# MotorShield.net
KiCad netlist of a schematic drawn in EAGLE
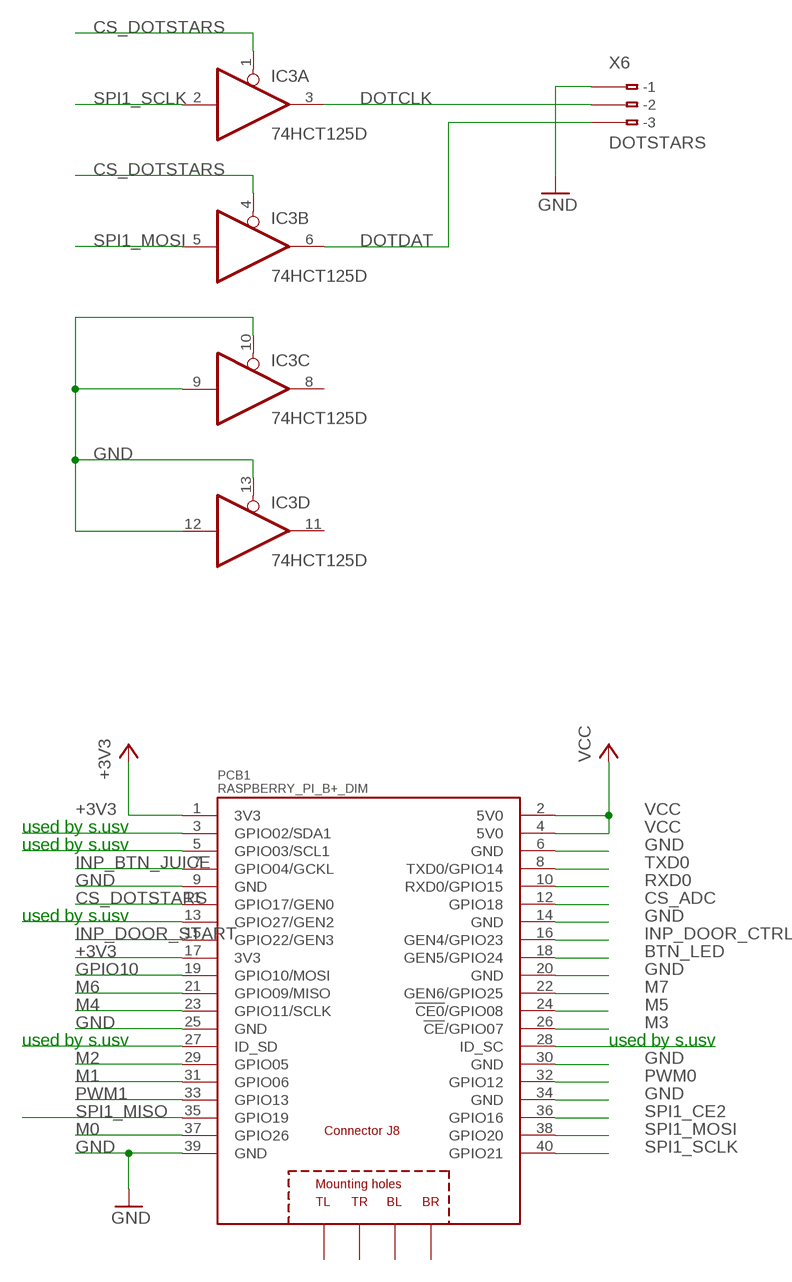
[diagram p0: schematic, sheet 1, part 1 of 2]
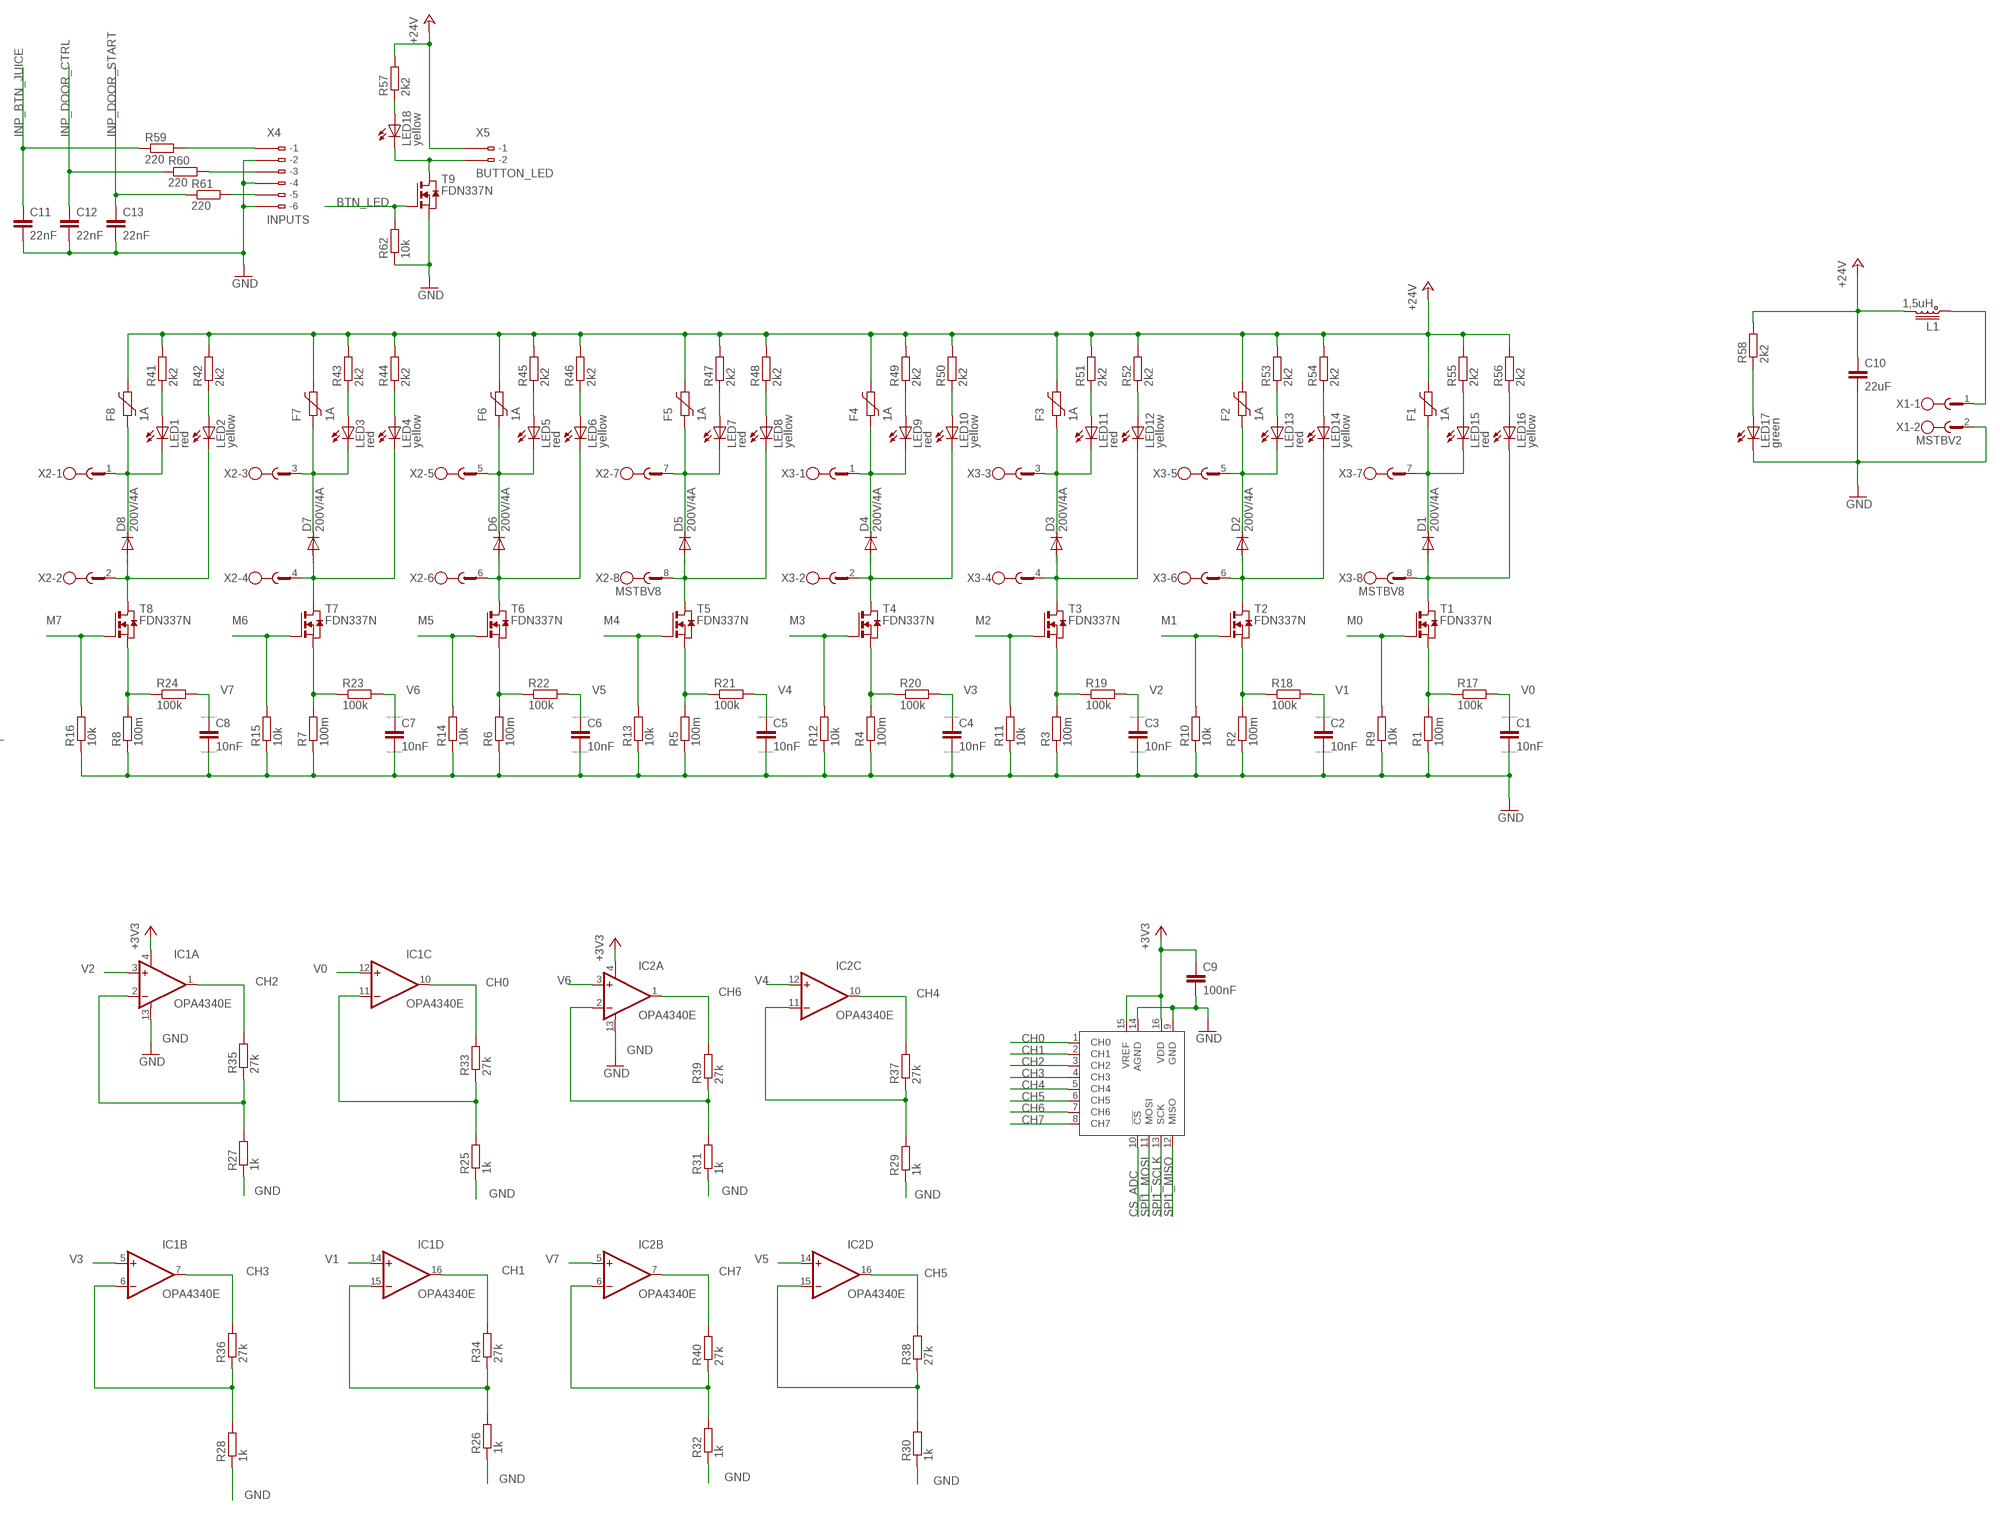
[diagram p1: schematic, sheet 1, part 2 of 2]

(export (version "E")
  (design (tool "Eeschema 10.0.6"))
  (components
    (comp (ref "C1")
      (value "10nF")
      (footprint "eagle-import:C0805")
      (libsource (lib "eagle-import") (part "C"))
    )
    (comp (ref "C2")
      (value "10nF")
      (footprint "eagle-import:C0805")
      (libsource (lib "eagle-import") (part "C"))
    )
    (comp (ref "C3")
      (value "10nF")
      (footprint "eagle-import:C0805")
      (libsource (lib "eagle-import") (part "C"))
    )
    (comp (ref "C4")
      (value "10nF")
      (footprint "eagle-import:C0805")
      (libsource (lib "eagle-import") (part "C"))
    )
    (comp (ref "C5")
      (value "10nF")
      (footprint "eagle-import:C0805")
      (libsource (lib "eagle-import") (part "C"))
    )
    (comp (ref "C6")
      (value "10nF")
      (footprint "eagle-import:C0805")
      (libsource (lib "eagle-import") (part "C"))
    )
    (comp (ref "C7")
      (value "10nF")
      (footprint "eagle-import:C0805")
      (libsource (lib "eagle-import") (part "C"))
    )
    (comp (ref "C8")
      (value "10nF")
      (footprint "eagle-import:C0805")
      (libsource (lib "eagle-import") (part "C"))
    )
    (comp (ref "C9")
      (value "100nF")
      (footprint "eagle-import:C0805")
      (libsource (lib "eagle-import") (part "C-EUC0805"))
    )
    (comp (ref "C10")
      (value "22uF")
      (footprint "eagle-import:C1812")
      (libsource (lib "eagle-import") (part "C-EUC1812"))
    )
    (comp (ref "C11")
      (value "22nF")
      (footprint "eagle-import:C0805K")
      (libsource (lib "eagle-import") (part "C-EUC0805K"))
    )
    (comp (ref "C12")
      (value "22nF")
      (footprint "eagle-import:C0805K")
      (libsource (lib "eagle-import") (part "C-EUC0805K"))
    )
    (comp (ref "C13")
      (value "22nF")
      (footprint "eagle-import:C0805K")
      (libsource (lib "eagle-import") (part "C-EUC0805K"))
    )
    (comp (ref "D1")
      (value "200V/4A")
      (footprint "eagle-import:DO214AA")
      (libsource (lib "eagle-import") (part "DIODE-DO214AA"))
    )
    (comp (ref "D2")
      (value "200V/4A")
      (footprint "eagle-import:DO214AA")
      (libsource (lib "eagle-import") (part "DIODE-DO214AA"))
    )
    (comp (ref "D3")
      (value "200V/4A")
      (footprint "eagle-import:DO214AA")
      (libsource (lib "eagle-import") (part "DIODE-DO214AA"))
    )
    (comp (ref "D4")
      (value "200V/4A")
      (footprint "eagle-import:DO214AA")
      (libsource (lib "eagle-import") (part "DIODE-DO214AA"))
    )
    (comp (ref "D5")
      (value "200V/4A")
      (footprint "eagle-import:DO214AA")
      (libsource (lib "eagle-import") (part "DIODE-DO214AA"))
    )
    (comp (ref "D6")
      (value "200V/4A")
      (footprint "eagle-import:DO214AA")
      (libsource (lib "eagle-import") (part "DIODE-DO214AA"))
    )
    (comp (ref "D7")
      (value "200V/4A")
      (footprint "eagle-import:DO214AA")
      (libsource (lib "eagle-import") (part "DIODE-DO214AA"))
    )
    (comp (ref "D8")
      (value "200V/4A")
      (footprint "eagle-import:DO214AA")
      (libsource (lib "eagle-import") (part "DIODE-DO214AA"))
    )
    (comp (ref "F1")
      (value "1A")
      (footprint "eagle-import:1812L")
      (libsource (lib "eagle-import") (part "1812L"))
    )
    (comp (ref "F2")
      (value "1A")
      (footprint "eagle-import:1812L")
      (libsource (lib "eagle-import") (part "1812L"))
    )
    (comp (ref "F3")
      (value "1A")
      (footprint "eagle-import:1812L")
      (libsource (lib "eagle-import") (part "1812L"))
    )
    (comp (ref "F4")
      (value "1A")
      (footprint "eagle-import:1812L")
      (libsource (lib "eagle-import") (part "1812L"))
    )
    (comp (ref "F5")
      (value "1A")
      (footprint "eagle-import:1812L")
      (libsource (lib "eagle-import") (part "1812L"))
    )
    (comp (ref "F6")
      (value "1A")
      (footprint "eagle-import:1812L")
      (libsource (lib "eagle-import") (part "1812L"))
    )
    (comp (ref "F7")
      (value "1A")
      (footprint "eagle-import:1812L")
      (libsource (lib "eagle-import") (part "1812L"))
    )
    (comp (ref "F8")
      (value "1A")
      (footprint "eagle-import:1812L")
      (libsource (lib "eagle-import") (part "1812L"))
    )
    (comp (ref "IC1")
      (value "OPA4340E")
      (footprint "eagle-import:SSOP16BU")
      (fields (field (name "MPN") "OPA4340EA/250G4"))
      (libsource (lib "eagle-import") (part "OPA4340E"))
    )
    (comp (ref "IC2")
      (value "OPA4340E")
      (footprint "eagle-import:SSOP16BU")
      (fields (field (name "MPN") "OPA4340EA/250G4"))
      (libsource (lib "eagle-import") (part "OPA4340E"))
    )
    (comp (ref "IC3")
      (value "74HCT125D")
      (footprint "eagle-import:SO14")
      (libsource (lib "eagle-import") (part "74125DHCT"))
    )
    (comp (ref "IC4")
      (value "MCP3008SL")
      (footprint "eagle-import:SO16")
      (libsource (lib "eagle-import") (part "MCP3008SL"))
    )
    (comp (ref "L1")
      (value "1,5uH")
      (footprint "eagle-import:MPI4040")
      (libsource (lib "eagle-import") (part "MPI4040R3-1R5-R"))
    )
    (comp (ref "LED1")
      (value "red")
      (footprint "eagle-import:CHIP-LED0805")
      (libsource (lib "eagle-import") (part "LEDCHIP-LED0805"))
    )
    (comp (ref "LED2")
      (value "yellow")
      (footprint "eagle-import:CHIP-LED0805")
      (libsource (lib "eagle-import") (part "LEDCHIP-LED0805"))
    )
    (comp (ref "LED3")
      (value "red")
      (footprint "eagle-import:CHIP-LED0805")
      (libsource (lib "eagle-import") (part "LEDCHIP-LED0805"))
    )
    (comp (ref "LED4")
      (value "yellow")
      (footprint "eagle-import:CHIP-LED0805")
      (libsource (lib "eagle-import") (part "LEDCHIP-LED0805"))
    )
    (comp (ref "LED5")
      (value "red")
      (footprint "eagle-import:CHIP-LED0805")
      (libsource (lib "eagle-import") (part "LEDCHIP-LED0805"))
    )
    (comp (ref "LED6")
      (value "yellow")
      (footprint "eagle-import:CHIP-LED0805")
      (libsource (lib "eagle-import") (part "LEDCHIP-LED0805"))
    )
    (comp (ref "LED7")
      (value "red")
      (footprint "eagle-import:CHIP-LED0805")
      (libsource (lib "eagle-import") (part "LEDCHIP-LED0805"))
    )
    (comp (ref "LED8")
      (value "yellow")
      (footprint "eagle-import:CHIP-LED0805")
      (libsource (lib "eagle-import") (part "LEDCHIP-LED0805"))
    )
    (comp (ref "LED9")
      (value "red")
      (footprint "eagle-import:CHIP-LED0805")
      (libsource (lib "eagle-import") (part "LEDCHIP-LED0805"))
    )
    (comp (ref "LED10")
      (value "yellow")
      (footprint "eagle-import:CHIP-LED0805")
      (libsource (lib "eagle-import") (part "LEDCHIP-LED0805"))
    )
    (comp (ref "LED11")
      (value "red")
      (footprint "eagle-import:CHIP-LED0805")
      (libsource (lib "eagle-import") (part "LEDCHIP-LED0805"))
    )
    (comp (ref "LED12")
      (value "yellow")
      (footprint "eagle-import:CHIP-LED0805")
      (libsource (lib "eagle-import") (part "LEDCHIP-LED0805"))
    )
    (comp (ref "LED13")
      (value "red")
      (footprint "eagle-import:CHIP-LED0805")
      (libsource (lib "eagle-import") (part "LEDCHIP-LED0805"))
    )
    (comp (ref "LED14")
      (value "yellow")
      (footprint "eagle-import:CHIP-LED0805")
      (libsource (lib "eagle-import") (part "LEDCHIP-LED0805"))
    )
    (comp (ref "LED15")
      (value "red")
      (footprint "eagle-import:CHIP-LED0805")
      (libsource (lib "eagle-import") (part "LEDCHIP-LED0805"))
    )
    (comp (ref "LED16")
      (value "yellow")
      (footprint "eagle-import:CHIP-LED0805")
      (libsource (lib "eagle-import") (part "LEDCHIP-LED0805"))
    )
    (comp (ref "LED17")
      (value "green")
      (footprint "eagle-import:CHIP-LED0805")
      (libsource (lib "eagle-import") (part "LEDCHIP-LED0805"))
    )
    (comp (ref "LED18")
      (value "yellow")
      (footprint "eagle-import:CHIP-LED0805")
      (libsource (lib "eagle-import") (part "LEDCHIP-LED0805"))
    )
    (comp (ref "PCB1")
      (value "RASPBERRY_PI_B+_DIM")
      (footprint "eagle-import:RASPBERRY_PI_BPLUS_DIM")
      (libsource (lib "eagle-import") (part "RASPBERRY_PI_B+_DIM"))
    )
    (comp (ref "R1")
      (value "100m")
      (footprint "eagle-import:R0805")
      (libsource (lib "eagle-import") (part "R-EU_R0805"))
    )
    (comp (ref "R2")
      (value "100m")
      (footprint "eagle-import:R0805")
      (libsource (lib "eagle-import") (part "R-EU_R0805"))
    )
    (comp (ref "R3")
      (value "100m")
      (footprint "eagle-import:R0805")
      (libsource (lib "eagle-import") (part "R-EU_R0805"))
    )
    (comp (ref "R4")
      (value "100m")
      (footprint "eagle-import:R0805")
      (libsource (lib "eagle-import") (part "R-EU_R0805"))
    )
    (comp (ref "R5")
      (value "100m")
      (footprint "eagle-import:R0805")
      (libsource (lib "eagle-import") (part "R-EU_R0805"))
    )
    (comp (ref "R6")
      (value "100m")
      (footprint "eagle-import:R0805")
      (libsource (lib "eagle-import") (part "R-EU_R0805"))
    )
    (comp (ref "R7")
      (value "100m")
      (footprint "eagle-import:R0805")
      (libsource (lib "eagle-import") (part "R-EU_R0805"))
    )
    (comp (ref "R8")
      (value "100m")
      (footprint "eagle-import:R0805")
      (libsource (lib "eagle-import") (part "R-EU_R0805"))
    )
    (comp (ref "R9")
      (value "10k")
      (footprint "eagle-import:R0805")
      (libsource (lib "eagle-import") (part "R-EU_R0805"))
    )
    (comp (ref "R10")
      (value "10k")
      (footprint "eagle-import:R0805")
      (libsource (lib "eagle-import") (part "R-EU_R0805"))
    )
    (comp (ref "R11")
      (value "10k")
      (footprint "eagle-import:R0805")
      (libsource (lib "eagle-import") (part "R-EU_R0805"))
    )
    (comp (ref "R12")
      (value "10k")
      (footprint "eagle-import:R0805")
      (libsource (lib "eagle-import") (part "R-EU_R0805"))
    )
    (comp (ref "R13")
      (value "10k")
      (footprint "eagle-import:R0805")
      (libsource (lib "eagle-import") (part "R-EU_R0805"))
    )
    (comp (ref "R14")
      (value "10k")
      (footprint "eagle-import:R0805")
      (libsource (lib "eagle-import") (part "R-EU_R0805"))
    )
    (comp (ref "R15")
      (value "10k")
      (footprint "eagle-import:R0805")
      (libsource (lib "eagle-import") (part "R-EU_R0805"))
    )
    (comp (ref "R16")
      (value "10k")
      (footprint "eagle-import:R0805")
      (libsource (lib "eagle-import") (part "R-EU_R0805"))
    )
    (comp (ref "R17")
      (value "100k")
      (footprint "eagle-import:R0805")
      (libsource (lib "eagle-import") (part "R-EU_R0805"))
    )
    (comp (ref "R18")
      (value "100k")
      (footprint "eagle-import:R0805")
      (libsource (lib "eagle-import") (part "R-EU_R0805"))
    )
    (comp (ref "R19")
      (value "100k")
      (footprint "eagle-import:R0805")
      (libsource (lib "eagle-import") (part "R-EU_R0805"))
    )
    (comp (ref "R20")
      (value "100k")
      (footprint "eagle-import:R0805")
      (libsource (lib "eagle-import") (part "R-EU_R0805"))
    )
    (comp (ref "R21")
      (value "100k")
      (footprint "eagle-import:R0805")
      (libsource (lib "eagle-import") (part "R-EU_R0805"))
    )
    (comp (ref "R22")
      (value "100k")
      (footprint "eagle-import:R0805")
      (libsource (lib "eagle-import") (part "R-EU_R0805"))
    )
    (comp (ref "R23")
      (value "100k")
      (footprint "eagle-import:R0805")
      (libsource (lib "eagle-import") (part "R-EU_R0805"))
    )
    (comp (ref "R24")
      (value "100k")
      (footprint "eagle-import:R0805")
      (libsource (lib "eagle-import") (part "R-EU_R0805"))
    )
    (comp (ref "R25")
      (value "1k")
      (footprint "eagle-import:R0805")
      (libsource (lib "eagle-import") (part "R-EU_R0805"))
    )
    (comp (ref "R26")
      (value "1k")
      (footprint "eagle-import:R0805")
      (libsource (lib "eagle-import") (part "R-EU_R0805"))
    )
    (comp (ref "R27")
      (value "1k")
      (footprint "eagle-import:R0805")
      (libsource (lib "eagle-import") (part "R-EU_R0805"))
    )
    (comp (ref "R28")
      (value "1k")
      (footprint "eagle-import:R0805")
      (libsource (lib "eagle-import") (part "R-EU_R0805"))
    )
    (comp (ref "R29")
      (value "1k")
      (footprint "eagle-import:R0805")
      (libsource (lib "eagle-import") (part "R-EU_R0805"))
    )
    (comp (ref "R30")
      (value "1k")
      (footprint "eagle-import:R0805")
      (libsource (lib "eagle-import") (part "R-EU_R0805"))
    )
    (comp (ref "R31")
      (value "1k")
      (footprint "eagle-import:R0805")
      (libsource (lib "eagle-import") (part "R-EU_R0805"))
    )
    (comp (ref "R32")
      (value "1k")
      (footprint "eagle-import:R0805")
      (libsource (lib "eagle-import") (part "R-EU_R0805"))
    )
    (comp (ref "R33")
      (value "27k")
      (footprint "eagle-import:R0805")
      (libsource (lib "eagle-import") (part "R-EU_R0805"))
    )
    (comp (ref "R34")
      (value "27k")
      (footprint "eagle-import:R0805")
      (libsource (lib "eagle-import") (part "R-EU_R0805"))
    )
    (comp (ref "R35")
      (value "27k")
      (footprint "eagle-import:R0805")
      (libsource (lib "eagle-import") (part "R-EU_R0805"))
    )
    (comp (ref "R36")
      (value "27k")
      (footprint "eagle-import:R0805")
      (libsource (lib "eagle-import") (part "R-EU_R0805"))
    )
    (comp (ref "R37")
      (value "27k")
      (footprint "eagle-import:R0805")
      (libsource (lib "eagle-import") (part "R-EU_R0805"))
    )
    (comp (ref "R38")
      (value "27k")
      (footprint "eagle-import:R0805")
      (libsource (lib "eagle-import") (part "R-EU_R0805"))
    )
    (comp (ref "R39")
      (value "27k")
      (footprint "eagle-import:R0805")
      (libsource (lib "eagle-import") (part "R-EU_R0805"))
    )
    (comp (ref "R40")
      (value "27k")
      (footprint "eagle-import:R0805")
      (libsource (lib "eagle-import") (part "R-EU_R0805"))
    )
    (comp (ref "R41")
      (value "2k2")
      (footprint "eagle-import:R0805")
      (libsource (lib "eagle-import") (part "R-EU_R0805"))
    )
    (comp (ref "R42")
      (value "2k2")
      (footprint "eagle-import:R0805")
      (libsource (lib "eagle-import") (part "R-EU_R0805"))
    )
    (comp (ref "R43")
      (value "2k2")
      (footprint "eagle-import:R0805")
      (libsource (lib "eagle-import") (part "R-EU_R0805"))
    )
    (comp (ref "R44")
      (value "2k2")
      (footprint "eagle-import:R0805")
      (libsource (lib "eagle-import") (part "R-EU_R0805"))
    )
    (comp (ref "R45")
      (value "2k2")
      (footprint "eagle-import:R0805")
      (libsource (lib "eagle-import") (part "R-EU_R0805"))
    )
    (comp (ref "R46")
      (value "2k2")
      (footprint "eagle-import:R0805")
      (libsource (lib "eagle-import") (part "R-EU_R0805"))
    )
    (comp (ref "R47")
      (value "2k2")
      (footprint "eagle-import:R0805")
      (libsource (lib "eagle-import") (part "R-EU_R0805"))
    )
    (comp (ref "R48")
      (value "2k2")
      (footprint "eagle-import:R0805")
      (libsource (lib "eagle-import") (part "R-EU_R0805"))
    )
    (comp (ref "R49")
      (value "2k2")
      (footprint "eagle-import:R0805")
      (libsource (lib "eagle-import") (part "R-EU_R0805"))
    )
    (comp (ref "R50")
      (value "2k2")
      (footprint "eagle-import:R0805")
      (libsource (lib "eagle-import") (part "R-EU_R0805"))
    )
    (comp (ref "R51")
      (value "2k2")
      (footprint "eagle-import:R0805")
      (libsource (lib "eagle-import") (part "R-EU_R0805"))
    )
    (comp (ref "R52")
      (value "2k2")
      (footprint "eagle-import:R0805")
      (libsource (lib "eagle-import") (part "R-EU_R0805"))
    )
    (comp (ref "R53")
      (value "2k2")
      (footprint "eagle-import:R0805")
      (libsource (lib "eagle-import") (part "R-EU_R0805"))
    )
    (comp (ref "R54")
      (value "2k2")
      (footprint "eagle-import:R0805")
      (libsource (lib "eagle-import") (part "R-EU_R0805"))
    )
    (comp (ref "R55")
      (value "2k2")
      (footprint "eagle-import:R0805")
      (libsource (lib "eagle-import") (part "R-EU_R0805"))
    )
    (comp (ref "R56")
      (value "2k2")
      (footprint "eagle-import:R0805")
      (libsource (lib "eagle-import") (part "R-EU_R0805"))
    )
    (comp (ref "R57")
      (value "2k2")
      (footprint "eagle-import:R0805")
      (libsource (lib "eagle-import") (part "R-EU_R0805"))
    )
    (comp (ref "R58")
      (value "2k2")
      (footprint "eagle-import:R0805")
      (libsource (lib "eagle-import") (part "R-EU_R0805"))
    )
    (comp (ref "R59")
      (value "220")
      (footprint "eagle-import:R0805")
      (libsource (lib "eagle-import") (part "R-EU_R0805"))
    )
    (comp (ref "R60")
      (value "220")
      (footprint "eagle-import:R0805")
      (libsource (lib "eagle-import") (part "R-EU_R0805"))
    )
    (comp (ref "R61")
      (value "220")
      (footprint "eagle-import:R0805")
      (libsource (lib "eagle-import") (part "R-EU_R0805"))
    )
    (comp (ref "R62")
      (value "10k")
      (footprint "eagle-import:R0805")
      (libsource (lib "eagle-import") (part "R-EU_R0805"))
    )
    (comp (ref "T1")
      (value "FDN337N")
      (footprint "eagle-import:SOT-23")
      (libsource (lib "eagle-import") (part "NMOSSOT23"))
    )
    (comp (ref "T2")
      (value "FDN337N")
      (footprint "eagle-import:SOT-23")
      (libsource (lib "eagle-import") (part "NMOSSOT23"))
    )
    (comp (ref "T3")
      (value "FDN337N")
      (footprint "eagle-import:SOT-23")
      (libsource (lib "eagle-import") (part "NMOSSOT23"))
    )
    (comp (ref "T4")
      (value "FDN337N")
      (footprint "eagle-import:SOT-23")
      (libsource (lib "eagle-import") (part "NMOSSOT23"))
    )
    (comp (ref "T5")
      (value "FDN337N")
      (footprint "eagle-import:SOT-23")
      (libsource (lib "eagle-import") (part "NMOSSOT23"))
    )
    (comp (ref "T6")
      (value "FDN337N")
      (footprint "eagle-import:SOT-23")
      (libsource (lib "eagle-import") (part "NMOSSOT23"))
    )
    (comp (ref "T7")
      (value "FDN337N")
      (footprint "eagle-import:SOT-23")
      (libsource (lib "eagle-import") (part "NMOSSOT23"))
    )
    (comp (ref "T8")
      (value "FDN337N")
      (footprint "eagle-import:SOT-23")
      (libsource (lib "eagle-import") (part "NMOSSOT23"))
    )
    (comp (ref "T9")
      (value "FDN337N")
      (footprint "eagle-import:SOT-23")
      (libsource (lib "eagle-import") (part "NMOSSOT23"))
    )
    (comp (ref "X1")
      (value "MSTBV2")
      (footprint "eagle-import:MSTBV2")
      (fields (field (name "MPN") "MSTBV 2,5/2-GF-5.08"))
      (libsource (lib "eagle-import") (part "MSTBV2"))
    )
    (comp (ref "X2")
      (value "MSTBV8")
      (footprint "eagle-import:MSTBV8")
      (fields (field (name "MPN") "MSTBV 2,5/8-GF-5.08"))
      (libsource (lib "eagle-import") (part "MSTBV8"))
    )
    (comp (ref "X3")
      (value "MSTBV8")
      (footprint "eagle-import:MSTBV8")
      (fields (field (name "MPN") "MSTBV 2,5/8-GF-5.08") (field (name "REICHELT") "RND 205-00392"))
      (libsource (lib "eagle-import") (part "MSTBV8"))
    )
    (comp (ref "X4")
      (value "INPUTS")
      (footprint "eagle-import:233-506")
      (fields (field (name "MF") "Wago Corporation") (field (name "MPN") "0233-0506"))
      (libsource (lib "eagle-import") (part "233-506"))
    )
    (comp (ref "X5")
      (value "BUTTON_LED")
      (footprint "eagle-import:233-502")
      (fields (field (name "MPN") "233-502"))
      (libsource (lib "eagle-import") (part "233-502"))
    )
    (comp (ref "X6")
      (value "DOTSTARS")
      (footprint "eagle-import:233-503")
      (fields (field (name "MF") "Wago Corporation") (field (name "MPN") "0233-0503"))
      (libsource (lib "eagle-import") (part "233-503"))
    )
  )
  (nets
    (net (code "1") (name "+3V3") (class "Default")
      (node (ref "C9") (pin "1") (pinfunction "1_1") (pintype "passive"))
      (node (ref "IC1") (pin "4") (pinfunction "V+_4") (pintype "power_in"))
      (node (ref "IC2") (pin "4") (pinfunction "V+_4") (pintype "power_in"))
      (node (ref "IC4") (pin "15") (pinfunction "VREF_15") (pintype "power_in"))
      (node (ref "IC4") (pin "16") (pinfunction "VDD_16") (pintype "power_in"))
      (node (ref "PCB1") (pin "1") (pinfunction "3V3_1") (pintype "power_in"))
      (node (ref "PCB1") (pin "17") (pinfunction "3V3_17") (pintype "power_in"))
    )
    (net (code "2") (name "+24V") (class "Default")
      (node (ref "C10") (pin "1") (pinfunction "1_1") (pintype "passive"))
      (node (ref "F1") (pin "2") (pinfunction "2_2") (pintype "passive"))
      (node (ref "F2") (pin "2") (pinfunction "2_2") (pintype "passive"))
      (node (ref "F3") (pin "2") (pinfunction "2_2") (pintype "passive"))
      (node (ref "F4") (pin "2") (pinfunction "2_2") (pintype "passive"))
      (node (ref "F5") (pin "2") (pinfunction "2_2") (pintype "passive"))
      (node (ref "F6") (pin "2") (pinfunction "2_2") (pintype "passive"))
      (node (ref "F7") (pin "2") (pinfunction "2_2") (pintype "passive"))
      (node (ref "F8") (pin "2") (pinfunction "2_2") (pintype "passive"))
      (node (ref "L1") (pin "2") (pinfunction "P$2_2") (pintype "bidirectional"))
      (node (ref "R41") (pin "2") (pinfunction "2_2") (pintype "passive"))
      (node (ref "R42") (pin "2") (pinfunction "2_2") (pintype "passive"))
      (node (ref "R43") (pin "2") (pinfunction "2_2") (pintype "passive"))
      (node (ref "R44") (pin "2") (pinfunction "2_2") (pintype "passive"))
      (node (ref "R45") (pin "2") (pinfunction "2_2") (pintype "passive"))
      (node (ref "R46") (pin "2") (pinfunction "2_2") (pintype "passive"))
      (node (ref "R47") (pin "2") (pinfunction "2_2") (pintype "passive"))
      (node (ref "R48") (pin "2") (pinfunction "2_2") (pintype "passive"))
      (node (ref "R49") (pin "2") (pinfunction "2_2") (pintype "passive"))
      (node (ref "R50") (pin "2") (pinfunction "2_2") (pintype "passive"))
      (node (ref "R51") (pin "2") (pinfunction "2_2") (pintype "passive"))
      (node (ref "R52") (pin "2") (pinfunction "2_2") (pintype "passive"))
      (node (ref "R53") (pin "2") (pinfunction "2_2") (pintype "passive"))
      (node (ref "R54") (pin "2") (pinfunction "2_2") (pintype "passive"))
      (node (ref "R55") (pin "2") (pinfunction "2_2") (pintype "passive"))
      (node (ref "R56") (pin "2") (pinfunction "2_2") (pintype "passive"))
      (node (ref "R57") (pin "2") (pinfunction "2_2") (pintype "passive"))
      (node (ref "R58") (pin "2") (pinfunction "2_2") (pintype "passive"))
      (node (ref "X5") (pin "B1") (pinfunction "B-1_B1") (pintype "passive"))
    )
    (net (code "3") (name "/BTN_LED") (class "Default")
      (node (ref "PCB1") (pin "18") (pinfunction "GEN5/GPIO24_18") (pintype "bidirectional"))
      (node (ref "R62") (pin "2") (pinfunction "2_2") (pintype "passive"))
      (node (ref "T9") (pin "3") (pinfunction "G_3") (pintype "passive"))
    )
    (net (code "4") (name "/CH0") (class "Default")
      (node (ref "IC1") (pin "10") (pinfunction "OUT_10") (pintype "output"))
      (node (ref "IC4") (pin "1") (pinfunction "CH0_1") (pintype "input"))
      (node (ref "R33") (pin "2") (pinfunction "2_2") (pintype "passive"))
    )
    (net (code "5") (name "/CH1") (class "Default")
      (node (ref "IC1") (pin "16") (pinfunction "OUT_16") (pintype "output"))
      (node (ref "IC4") (pin "2") (pinfunction "CH1_2") (pintype "input"))
      (node (ref "R34") (pin "2") (pinfunction "2_2") (pintype "passive"))
    )
    (net (code "6") (name "/CH2") (class "Default")
      (node (ref "IC1") (pin "1") (pinfunction "OUT_1") (pintype "output"))
      (node (ref "IC4") (pin "3") (pinfunction "CH2_3") (pintype "input"))
      (node (ref "R35") (pin "2") (pinfunction "2_2") (pintype "passive"))
    )
    (net (code "7") (name "/CH3") (class "Default")
      (node (ref "IC1") (pin "7") (pinfunction "OUT_7") (pintype "output"))
      (node (ref "IC4") (pin "4") (pinfunction "CH3_4") (pintype "input"))
      (node (ref "R36") (pin "2") (pinfunction "2_2") (pintype "passive"))
    )
    (net (code "8") (name "/CH4") (class "Default")
      (node (ref "IC2") (pin "10") (pinfunction "OUT_10") (pintype "output"))
      (node (ref "IC4") (pin "5") (pinfunction "CH4_5") (pintype "input"))
      (node (ref "R37") (pin "2") (pinfunction "2_2") (pintype "passive"))
    )
    (net (code "9") (name "/CH5") (class "Default")
      (node (ref "IC2") (pin "16") (pinfunction "OUT_16") (pintype "output"))
      (node (ref "IC4") (pin "6") (pinfunction "CH5_6") (pintype "input"))
      (node (ref "R38") (pin "2") (pinfunction "2_2") (pintype "passive"))
    )
    (net (code "10") (name "/CH6") (class "Default")
      (node (ref "IC2") (pin "1") (pinfunction "OUT_1") (pintype "output"))
      (node (ref "IC4") (pin "7") (pinfunction "CH6_7") (pintype "input"))
      (node (ref "R39") (pin "2") (pinfunction "2_2") (pintype "passive"))
    )
    (net (code "11") (name "/CH7") (class "Default")
      (node (ref "IC2") (pin "7") (pinfunction "OUT_7") (pintype "output"))
      (node (ref "IC4") (pin "8") (pinfunction "CH7_8") (pintype "input"))
      (node (ref "R40") (pin "2") (pinfunction "2_2") (pintype "passive"))
    )
    (net (code "12") (name "/CS_ADC") (class "Default")
      (node (ref "IC4") (pin "10") (pinfunction "~{CS}_10") (pintype "input"))
      (node (ref "PCB1") (pin "12") (pinfunction "GPIO18_12") (pintype "bidirectional"))
    )
    (net (code "13") (name "/CS_DOTSTARS") (class "Default")
      (node (ref "IC3") (pin "1") (pinfunction "OE_1") (pintype "input"))
      (node (ref "IC3") (pin "4") (pinfunction "OE_4") (pintype "input"))
      (node (ref "PCB1") (pin "11") (pinfunction "GPIO17/GEN0_11") (pintype "bidirectional"))
    )
    (net (code "14") (name "/DOTCLK") (class "Default")
      (node (ref "IC3") (pin "3") (pinfunction "O_3") (pintype "tri_state"))
      (node (ref "X6") (pin "B2") (pinfunction "B-2_B2") (pintype "passive"))
    )
    (net (code "15") (name "/DOTDAT") (class "Default")
      (node (ref "IC3") (pin "6") (pinfunction "O_6") (pintype "tri_state"))
      (node (ref "X6") (pin "B3") (pinfunction "B-3_B3") (pintype "passive"))
    )
    (net (code "16") (name "/GPIO10") (class "Default")
      (node (ref "PCB1") (pin "19") (pinfunction "GPIO10/MOSI_19") (pintype "bidirectional"))
    )
    (net (code "17") (name "/INP_BTN_JUICE") (class "Default")
      (node (ref "C11") (pin "1") (pinfunction "1_1") (pintype "passive"))
      (node (ref "PCB1") (pin "7") (pinfunction "GPIO04/GCKL_7") (pintype "bidirectional"))
      (node (ref "R59") (pin "1") (pinfunction "1_1") (pintype "passive"))
    )
    (net (code "18") (name "/INP_DOOR_CTRL") (class "Default")
      (node (ref "C12") (pin "1") (pinfunction "1_1") (pintype "passive"))
      (node (ref "PCB1") (pin "16") (pinfunction "GEN4/GPIO23_16") (pintype "bidirectional"))
      (node (ref "R60") (pin "1") (pinfunction "1_1") (pintype "passive"))
    )
    (net (code "19") (name "/INP_DOOR_START") (class "Default")
      (node (ref "C13") (pin "1") (pinfunction "1_1") (pintype "passive"))
      (node (ref "PCB1") (pin "15") (pinfunction "GPIO22/GEN3_15") (pintype "bidirectional"))
      (node (ref "R61") (pin "1") (pinfunction "1_1") (pintype "passive"))
    )
    (net (code "20") (name "/M0") (class "Default")
      (node (ref "PCB1") (pin "37") (pinfunction "GPIO26_37") (pintype "bidirectional"))
      (node (ref "R9") (pin "2") (pinfunction "2_2") (pintype "passive"))
      (node (ref "T1") (pin "3") (pinfunction "G_3") (pintype "passive"))
    )
    (net (code "21") (name "/M1") (class "Default")
      (node (ref "PCB1") (pin "31") (pinfunction "GPIO06_31") (pintype "bidirectional"))
      (node (ref "R10") (pin "2") (pinfunction "2_2") (pintype "passive"))
      (node (ref "T2") (pin "3") (pinfunction "G_3") (pintype "passive"))
    )
    (net (code "22") (name "/M2") (class "Default")
      (node (ref "PCB1") (pin "29") (pinfunction "GPIO05_29") (pintype "bidirectional"))
      (node (ref "R11") (pin "2") (pinfunction "2_2") (pintype "passive"))
      (node (ref "T3") (pin "3") (pinfunction "G_3") (pintype "passive"))
    )
    (net (code "23") (name "/M3") (class "Default")
      (node (ref "PCB1") (pin "26") (pinfunction "~{CE}/GPIO07_26") (pintype "bidirectional"))
      (node (ref "R12") (pin "2") (pinfunction "2_2") (pintype "passive"))
      (node (ref "T4") (pin "3") (pinfunction "G_3") (pintype "passive"))
    )
    (net (code "24") (name "/M4") (class "Default")
      (node (ref "PCB1") (pin "23") (pinfunction "GPIO11/SCLK_23") (pintype "bidirectional"))
      (node (ref "R13") (pin "2") (pinfunction "2_2") (pintype "passive"))
      (node (ref "T5") (pin "3") (pinfunction "G_3") (pintype "passive"))
    )
    (net (code "25") (name "/M5") (class "Default")
      (node (ref "PCB1") (pin "24") (pinfunction "~{CE0}/GPIO08_24") (pintype "bidirectional"))
      (node (ref "R14") (pin "2") (pinfunction "2_2") (pintype "passive"))
      (node (ref "T6") (pin "3") (pinfunction "G_3") (pintype "passive"))
    )
    (net (code "26") (name "/M6") (class "Default")
      (node (ref "PCB1") (pin "21") (pinfunction "GPIO09/MISO_21") (pintype "bidirectional"))
      (node (ref "R15") (pin "2") (pinfunction "2_2") (pintype "passive"))
      (node (ref "T7") (pin "3") (pinfunction "G_3") (pintype "passive"))
    )
    (net (code "27") (name "/M7") (class "Default")
      (node (ref "PCB1") (pin "22") (pinfunction "GEN6/GPIO25_22") (pintype "bidirectional"))
      (node (ref "R16") (pin "2") (pinfunction "2_2") (pintype "passive"))
      (node (ref "T8") (pin "3") (pinfunction "G_3") (pintype "passive"))
    )
    (net (code "28") (name "/PWM0") (class "Default")
      (node (ref "PCB1") (pin "32") (pinfunction "GPIO12_32") (pintype "bidirectional"))
    )
    (net (code "29") (name "/PWM1") (class "Default")
      (node (ref "PCB1") (pin "33") (pinfunction "GPIO13_33") (pintype "bidirectional"))
    )
    (net (code "30") (name "/RXD0") (class "Default")
      (node (ref "PCB1") (pin "10") (pinfunction "RXD0/GPIO15_10") (pintype "bidirectional"))
    )
    (net (code "31") (name "/SPI1_CE2") (class "Default")
      (node (ref "PCB1") (pin "36") (pinfunction "GPIO16_36") (pintype "bidirectional"))
    )
    (net (code "32") (name "/SPI1_MISO") (class "Default")
      (node (ref "IC4") (pin "12") (pinfunction "MISO_12") (pintype "output"))
      (node (ref "PCB1") (pin "35") (pinfunction "GPIO19_35") (pintype "bidirectional"))
    )
    (net (code "33") (name "/SPI1_MOSI") (class "Default")
      (node (ref "IC3") (pin "5") (pinfunction "I_5") (pintype "input"))
      (node (ref "IC4") (pin "11") (pinfunction "MOSI_11") (pintype "input"))
      (node (ref "PCB1") (pin "38") (pinfunction "GPIO20_38") (pintype "bidirectional"))
    )
    (net (code "34") (name "/SPI1_SCLK") (class "Default")
      (node (ref "IC3") (pin "2") (pinfunction "I_2") (pintype "input"))
      (node (ref "IC4") (pin "13") (pinfunction "SCK_13") (pintype "input"))
      (node (ref "PCB1") (pin "40") (pinfunction "GPIO21_40") (pintype "bidirectional"))
    )
    (net (code "35") (name "/TXD0") (class "Default")
      (node (ref "PCB1") (pin "8") (pinfunction "TXD0/GPIO14_8") (pintype "bidirectional"))
    )
    (net (code "36") (name "/V0") (class "Default")
      (node (ref "C1") (pin "1") (pinfunction "1_1") (pintype "passive"))
      (node (ref "IC1") (pin "12") (pinfunction "+IN_12") (pintype "input"))
      (node (ref "R17") (pin "2") (pinfunction "2_2") (pintype "passive"))
    )
    (net (code "37") (name "/V1") (class "Default")
      (node (ref "C2") (pin "1") (pinfunction "1_1") (pintype "passive"))
      (node (ref "IC1") (pin "14") (pinfunction "+IN_14") (pintype "input"))
      (node (ref "R18") (pin "2") (pinfunction "2_2") (pintype "passive"))
    )
    (net (code "38") (name "/V2") (class "Default")
      (node (ref "C3") (pin "1") (pinfunction "1_1") (pintype "passive"))
      (node (ref "IC1") (pin "3") (pinfunction "+IN_3") (pintype "input"))
      (node (ref "R19") (pin "2") (pinfunction "2_2") (pintype "passive"))
    )
    (net (code "39") (name "/V3") (class "Default")
      (node (ref "C4") (pin "1") (pinfunction "1_1") (pintype "passive"))
      (node (ref "IC1") (pin "5") (pinfunction "+IN_5") (pintype "input"))
      (node (ref "R20") (pin "2") (pinfunction "2_2") (pintype "passive"))
    )
    (net (code "40") (name "/V4") (class "Default")
      (node (ref "C5") (pin "1") (pinfunction "1_1") (pintype "passive"))
      (node (ref "IC2") (pin "12") (pinfunction "+IN_12") (pintype "input"))
      (node (ref "R21") (pin "2") (pinfunction "2_2") (pintype "passive"))
    )
    (net (code "41") (name "/V5") (class "Default")
      (node (ref "C6") (pin "1") (pinfunction "1_1") (pintype "passive"))
      (node (ref "IC2") (pin "14") (pinfunction "+IN_14") (pintype "input"))
      (node (ref "R22") (pin "2") (pinfunction "2_2") (pintype "passive"))
    )
    (net (code "42") (name "/V6") (class "Default")
      (node (ref "C7") (pin "1") (pinfunction "1_1") (pintype "passive"))
      (node (ref "IC2") (pin "3") (pinfunction "+IN_3") (pintype "input"))
      (node (ref "R23") (pin "2") (pinfunction "2_2") (pintype "passive"))
    )
    (net (code "43") (name "/V7") (class "Default")
      (node (ref "C8") (pin "1") (pinfunction "1_1") (pintype "passive"))
      (node (ref "IC2") (pin "5") (pinfunction "+IN_5") (pintype "input"))
      (node (ref "R24") (pin "2") (pinfunction "2_2") (pintype "passive"))
    )
    (net (code "44") (name "GND") (class "Default")
      (node (ref "C1") (pin "2") (pinfunction "2_2") (pintype "passive"))
      (node (ref "C10") (pin "2") (pinfunction "2_2") (pintype "passive"))
      (node (ref "C11") (pin "2") (pinfunction "2_2") (pintype "passive"))
      (node (ref "C12") (pin "2") (pinfunction "2_2") (pintype "passive"))
      (node (ref "C13") (pin "2") (pinfunction "2_2") (pintype "passive"))
      (node (ref "C2") (pin "2") (pinfunction "2_2") (pintype "passive"))
      (node (ref "C3") (pin "2") (pinfunction "2_2") (pintype "passive"))
      (node (ref "C4") (pin "2") (pinfunction "2_2") (pintype "passive"))
      (node (ref "C5") (pin "2") (pinfunction "2_2") (pintype "passive"))
      (node (ref "C6") (pin "2") (pinfunction "2_2") (pintype "passive"))
      (node (ref "C7") (pin "2") (pinfunction "2_2") (pintype "passive"))
      (node (ref "C8") (pin "2") (pinfunction "2_2") (pintype "passive"))
      (node (ref "C9") (pin "2") (pinfunction "2_2") (pintype "passive"))
      (node (ref "IC1") (pin "13") (pinfunction "V-_13") (pintype "power_in"))
      (node (ref "IC2") (pin "13") (pinfunction "V-_13") (pintype "power_in"))
      (node (ref "IC3") (pin "10") (pinfunction "OE_10") (pintype "input"))
      (node (ref "IC3") (pin "12") (pinfunction "I_12") (pintype "input"))
      (node (ref "IC3") (pin "13") (pinfunction "OE_13") (pintype "input"))
      (node (ref "IC3") (pin "9") (pinfunction "I_9") (pintype "input"))
      (node (ref "IC4") (pin "14") (pinfunction "AGND_14") (pintype "power_in"))
      (node (ref "IC4") (pin "9") (pinfunction "GND_9") (pintype "power_in"))
      (node (ref "LED17") (pin "C") (pinfunction "C_C") (pintype "passive"))
      (node (ref "PCB1") (pin "14") (pinfunction "GND_14") (pintype "power_in"))
      (node (ref "PCB1") (pin "20") (pinfunction "GND_20") (pintype "power_in"))
      (node (ref "PCB1") (pin "25") (pinfunction "GND_25") (pintype "power_in"))
      (node (ref "PCB1") (pin "30") (pinfunction "GND_30") (pintype "power_in"))
      (node (ref "PCB1") (pin "34") (pinfunction "GND_34") (pintype "power_in"))
      (node (ref "PCB1") (pin "39") (pinfunction "GND_39") (pintype "power_in"))
      (node (ref "PCB1") (pin "6") (pinfunction "GND_6") (pintype "power_in"))
      (node (ref "PCB1") (pin "9") (pinfunction "GND_9") (pintype "power_in"))
      (node (ref "R1") (pin "1") (pinfunction "1_1") (pintype "passive"))
      (node (ref "R10") (pin "1") (pinfunction "1_1") (pintype "passive"))
      (node (ref "R11") (pin "1") (pinfunction "1_1") (pintype "passive"))
      (node (ref "R12") (pin "1") (pinfunction "1_1") (pintype "passive"))
      (node (ref "R13") (pin "1") (pinfunction "1_1") (pintype "passive"))
      (node (ref "R14") (pin "1") (pinfunction "1_1") (pintype "passive"))
      (node (ref "R15") (pin "1") (pinfunction "1_1") (pintype "passive"))
      (node (ref "R16") (pin "1") (pinfunction "1_1") (pintype "passive"))
      (node (ref "R2") (pin "1") (pinfunction "1_1") (pintype "passive"))
      (node (ref "R25") (pin "1") (pinfunction "1_1") (pintype "passive"))
      (node (ref "R26") (pin "1") (pinfunction "1_1") (pintype "passive"))
      (node (ref "R27") (pin "1") (pinfunction "1_1") (pintype "passive"))
      (node (ref "R28") (pin "1") (pinfunction "1_1") (pintype "passive"))
      (node (ref "R29") (pin "1") (pinfunction "1_1") (pintype "passive"))
      (node (ref "R3") (pin "1") (pinfunction "1_1") (pintype "passive"))
      (node (ref "R30") (pin "1") (pinfunction "1_1") (pintype "passive"))
      (node (ref "R31") (pin "1") (pinfunction "1_1") (pintype "passive"))
      (node (ref "R32") (pin "1") (pinfunction "1_1") (pintype "passive"))
      (node (ref "R4") (pin "1") (pinfunction "1_1") (pintype "passive"))
      (node (ref "R5") (pin "1") (pinfunction "1_1") (pintype "passive"))
      (node (ref "R6") (pin "1") (pinfunction "1_1") (pintype "passive"))
      (node (ref "R62") (pin "1") (pinfunction "1_1") (pintype "passive"))
      (node (ref "R7") (pin "1") (pinfunction "1_1") (pintype "passive"))
      (node (ref "R8") (pin "1") (pinfunction "1_1") (pintype "passive"))
      (node (ref "R9") (pin "1") (pinfunction "1_1") (pintype "passive"))
      (node (ref "T9") (pin "2") (pinfunction "S_2") (pintype "passive"))
      (node (ref "X1") (pin "2") (pinfunction "1_2") (pintype "passive"))
      (node (ref "X4") (pin "B2") (pinfunction "B-2_B2") (pintype "passive"))
      (node (ref "X4") (pin "B4") (pinfunction "B-4_B4") (pintype "passive"))
      (node (ref "X4") (pin "B6") (pinfunction "B-6_B6") (pintype "passive"))
      (node (ref "X6") (pin "B1") (pinfunction "B-1_B1") (pintype "passive"))
    )
    (net (code "45") (name "Net-(D4-PadC)") (class "Default")
      (node (ref "D4") (pin "C") (pinfunction "C_C") (pintype "passive"))
      (node (ref "F4") (pin "1") (pinfunction "1_1") (pintype "passive"))
      (node (ref "LED9") (pin "C") (pinfunction "C_C") (pintype "passive"))
      (node (ref "X3") (pin "1") (pinfunction "1_1") (pintype "passive"))
    )
    (net (code "46") (name "Net-(D8-PadC)") (class "Default")
      (node (ref "D8") (pin "C") (pinfunction "C_C") (pintype "passive"))
      (node (ref "F8") (pin "1") (pinfunction "1_1") (pintype "passive"))
      (node (ref "LED1") (pin "C") (pinfunction "C_C") (pintype "passive"))
      (node (ref "X2") (pin "1") (pinfunction "1_1") (pintype "passive"))
    )
    (net (code "47") (name "Net-(IC1A--IN)") (class "Default")
      (node (ref "IC1") (pin "2") (pinfunction "-IN_2") (pintype "input"))
      (node (ref "R27") (pin "2") (pinfunction "2_2") (pintype "passive"))
      (node (ref "R35") (pin "1") (pinfunction "1_1") (pintype "passive"))
    )
    (net (code "48") (name "Net-(IC1B--IN)") (class "Default")
      (node (ref "IC1") (pin "6") (pinfunction "-IN_6") (pintype "input"))
      (node (ref "R28") (pin "2") (pinfunction "2_2") (pintype "passive"))
      (node (ref "R36") (pin "1") (pinfunction "1_1") (pintype "passive"))
    )
    (net (code "49") (name "Net-(IC1C--IN)") (class "Default")
      (node (ref "IC1") (pin "11") (pinfunction "-IN_11") (pintype "input"))
      (node (ref "R25") (pin "2") (pinfunction "2_2") (pintype "passive"))
      (node (ref "R33") (pin "1") (pinfunction "1_1") (pintype "passive"))
    )
    (net (code "50") (name "Net-(IC1D--IN)") (class "Default")
      (node (ref "IC1") (pin "15") (pinfunction "-IN_15") (pintype "input"))
      (node (ref "R26") (pin "2") (pinfunction "2_2") (pintype "passive"))
      (node (ref "R34") (pin "1") (pinfunction "1_1") (pintype "passive"))
    )
    (net (code "51") (name "Net-(IC2A--IN)") (class "Default")
      (node (ref "IC2") (pin "2") (pinfunction "-IN_2") (pintype "input"))
      (node (ref "R31") (pin "2") (pinfunction "2_2") (pintype "passive"))
      (node (ref "R39") (pin "1") (pinfunction "1_1") (pintype "passive"))
    )
    (net (code "52") (name "Net-(IC2B--IN)") (class "Default")
      (node (ref "IC2") (pin "6") (pinfunction "-IN_6") (pintype "input"))
      (node (ref "R32") (pin "2") (pinfunction "2_2") (pintype "passive"))
      (node (ref "R40") (pin "1") (pinfunction "1_1") (pintype "passive"))
    )
    (net (code "53") (name "Net-(IC2C--IN)") (class "Default")
      (node (ref "IC2") (pin "11") (pinfunction "-IN_11") (pintype "input"))
      (node (ref "R29") (pin "2") (pinfunction "2_2") (pintype "passive"))
      (node (ref "R37") (pin "1") (pinfunction "1_1") (pintype "passive"))
    )
    (net (code "54") (name "Net-(IC2D--IN)") (class "Default")
      (node (ref "IC2") (pin "15") (pinfunction "-IN_15") (pintype "input"))
      (node (ref "R30") (pin "2") (pinfunction "2_2") (pintype "passive"))
      (node (ref "R38") (pin "1") (pinfunction "1_1") (pintype "passive"))
    )
    (net (code "55") (name "Net-(L1-P$1)") (class "Default")
      (node (ref "L1") (pin "1") (pinfunction "P$1_1") (pintype "bidirectional"))
      (node (ref "X1") (pin "1") (pinfunction "1_1") (pintype "passive"))
    )
    (net (code "56") (name "Net-(LED1-PadA)") (class "Default")
      (node (ref "LED1") (pin "A") (pinfunction "A_A") (pintype "passive"))
      (node (ref "R41") (pin "1") (pinfunction "1_1") (pintype "passive"))
    )
    (net (code "57") (name "Net-(LED2-PadA)") (class "Default")
      (node (ref "LED2") (pin "A") (pinfunction "A_A") (pintype "passive"))
      (node (ref "R42") (pin "1") (pinfunction "1_1") (pintype "passive"))
    )
    (net (code "58") (name "Net-(LED3-PadA)") (class "Default")
      (node (ref "LED3") (pin "A") (pinfunction "A_A") (pintype "passive"))
      (node (ref "R43") (pin "1") (pinfunction "1_1") (pintype "passive"))
    )
    (net (code "59") (name "Net-(LED4-PadA)") (class "Default")
      (node (ref "LED4") (pin "A") (pinfunction "A_A") (pintype "passive"))
      (node (ref "R44") (pin "1") (pinfunction "1_1") (pintype "passive"))
    )
    (net (code "60") (name "Net-(LED5-PadA)") (class "Default")
      (node (ref "LED5") (pin "A") (pinfunction "A_A") (pintype "passive"))
      (node (ref "R45") (pin "1") (pinfunction "1_1") (pintype "passive"))
    )
    (net (code "61") (name "Net-(LED6-PadA)") (class "Default")
      (node (ref "LED6") (pin "A") (pinfunction "A_A") (pintype "passive"))
      (node (ref "R46") (pin "1") (pinfunction "1_1") (pintype "passive"))
    )
    (net (code "62") (name "Net-(LED7-PadA)") (class "Default")
      (node (ref "LED7") (pin "A") (pinfunction "A_A") (pintype "passive"))
      (node (ref "R47") (pin "1") (pinfunction "1_1") (pintype "passive"))
    )
    (net (code "63") (name "Net-(LED8-PadA)") (class "Default")
      (node (ref "LED8") (pin "A") (pinfunction "A_A") (pintype "passive"))
      (node (ref "R48") (pin "1") (pinfunction "1_1") (pintype "passive"))
    )
    (net (code "64") (name "Net-(LED9-PadA)") (class "Default")
      (node (ref "LED9") (pin "A") (pinfunction "A_A") (pintype "passive"))
      (node (ref "R49") (pin "1") (pinfunction "1_1") (pintype "passive"))
    )
    (net (code "65") (name "Net-(LED10-PadA)") (class "Default")
      (node (ref "LED10") (pin "A") (pinfunction "A_A") (pintype "passive"))
      (node (ref "R50") (pin "1") (pinfunction "1_1") (pintype "passive"))
    )
    (net (code "66") (name "Net-(LED11-PadA)") (class "Default")
      (node (ref "LED11") (pin "A") (pinfunction "A_A") (pintype "passive"))
      (node (ref "R51") (pin "1") (pinfunction "1_1") (pintype "passive"))
    )
    (net (code "67") (name "Net-(LED12-PadA)") (class "Default")
      (node (ref "LED12") (pin "A") (pinfunction "A_A") (pintype "passive"))
      (node (ref "R52") (pin "1") (pinfunction "1_1") (pintype "passive"))
    )
    (net (code "68") (name "Net-(LED13-PadA)") (class "Default")
      (node (ref "LED13") (pin "A") (pinfunction "A_A") (pintype "passive"))
      (node (ref "R53") (pin "1") (pinfunction "1_1") (pintype "passive"))
    )
    (net (code "69") (name "Net-(LED14-PadA)") (class "Default")
      (node (ref "LED14") (pin "A") (pinfunction "A_A") (pintype "passive"))
      (node (ref "R54") (pin "1") (pinfunction "1_1") (pintype "passive"))
    )
    (net (code "70") (name "Net-(LED15-PadA)") (class "Default")
      (node (ref "LED15") (pin "A") (pinfunction "A_A") (pintype "passive"))
      (node (ref "R55") (pin "1") (pinfunction "1_1") (pintype "passive"))
    )
    (net (code "71") (name "Net-(LED16-PadA)") (class "Default")
      (node (ref "LED16") (pin "A") (pinfunction "A_A") (pintype "passive"))
      (node (ref "R56") (pin "1") (pinfunction "1_1") (pintype "passive"))
    )
    (net (code "72") (name "Net-(LED17-PadA)") (class "Default")
      (node (ref "LED17") (pin "A") (pinfunction "A_A") (pintype "passive"))
      (node (ref "R58") (pin "1") (pinfunction "1_1") (pintype "passive"))
    )
    (net (code "73") (name "Net-(LED18-PadA)") (class "Default")
      (node (ref "LED18") (pin "A") (pinfunction "A_A") (pintype "passive"))
      (node (ref "R57") (pin "1") (pinfunction "1_1") (pintype "passive"))
    )
    (net (code "74") (name "Net-(T1-D)") (class "Default")
      (node (ref "D1") (pin "A") (pinfunction "A_A") (pintype "passive"))
      (node (ref "LED16") (pin "C") (pinfunction "C_C") (pintype "passive"))
      (node (ref "T1") (pin "1") (pinfunction "D_1") (pintype "passive"))
      (node (ref "X3") (pin "8") (pinfunction "1_8") (pintype "passive"))
    )
    (net (code "75") (name "Net-(T1-S)") (class "Default")
      (node (ref "R1") (pin "2") (pinfunction "2_2") (pintype "passive"))
      (node (ref "R17") (pin "1") (pinfunction "1_1") (pintype "passive"))
      (node (ref "T1") (pin "2") (pinfunction "S_2") (pintype "passive"))
    )
    (net (code "76") (name "Net-(T2-D)") (class "Default")
      (node (ref "D2") (pin "A") (pinfunction "A_A") (pintype "passive"))
      (node (ref "LED14") (pin "C") (pinfunction "C_C") (pintype "passive"))
      (node (ref "T2") (pin "1") (pinfunction "D_1") (pintype "passive"))
      (node (ref "X3") (pin "6") (pinfunction "1_6") (pintype "passive"))
    )
    (net (code "77") (name "Net-(T2-S)") (class "Default")
      (node (ref "R18") (pin "1") (pinfunction "1_1") (pintype "passive"))
      (node (ref "R2") (pin "2") (pinfunction "2_2") (pintype "passive"))
      (node (ref "T2") (pin "2") (pinfunction "S_2") (pintype "passive"))
    )
    (net (code "78") (name "Net-(T3-D)") (class "Default")
      (node (ref "D3") (pin "A") (pinfunction "A_A") (pintype "passive"))
      (node (ref "LED12") (pin "C") (pinfunction "C_C") (pintype "passive"))
      (node (ref "T3") (pin "1") (pinfunction "D_1") (pintype "passive"))
      (node (ref "X3") (pin "4") (pinfunction "1_4") (pintype "passive"))
    )
    (net (code "79") (name "Net-(T3-S)") (class "Default")
      (node (ref "R19") (pin "1") (pinfunction "1_1") (pintype "passive"))
      (node (ref "R3") (pin "2") (pinfunction "2_2") (pintype "passive"))
      (node (ref "T3") (pin "2") (pinfunction "S_2") (pintype "passive"))
    )
    (net (code "80") (name "Net-(T4-D)") (class "Default")
      (node (ref "D4") (pin "A") (pinfunction "A_A") (pintype "passive"))
      (node (ref "LED10") (pin "C") (pinfunction "C_C") (pintype "passive"))
      (node (ref "T4") (pin "1") (pinfunction "D_1") (pintype "passive"))
      (node (ref "X3") (pin "2") (pinfunction "1_2") (pintype "passive"))
    )
    (net (code "81") (name "Net-(T4-S)") (class "Default")
      (node (ref "R20") (pin "1") (pinfunction "1_1") (pintype "passive"))
      (node (ref "R4") (pin "2") (pinfunction "2_2") (pintype "passive"))
      (node (ref "T4") (pin "2") (pinfunction "S_2") (pintype "passive"))
    )
    (net (code "82") (name "Net-(T5-D)") (class "Default")
      (node (ref "D5") (pin "A") (pinfunction "A_A") (pintype "passive"))
      (node (ref "LED8") (pin "C") (pinfunction "C_C") (pintype "passive"))
      (node (ref "T5") (pin "1") (pinfunction "D_1") (pintype "passive"))
      (node (ref "X2") (pin "8") (pinfunction "1_8") (pintype "passive"))
    )
    (net (code "83") (name "Net-(T5-S)") (class "Default")
      (node (ref "R21") (pin "1") (pinfunction "1_1") (pintype "passive"))
      (node (ref "R5") (pin "2") (pinfunction "2_2") (pintype "passive"))
      (node (ref "T5") (pin "2") (pinfunction "S_2") (pintype "passive"))
    )
    (net (code "84") (name "Net-(T6-D)") (class "Default")
      (node (ref "D6") (pin "A") (pinfunction "A_A") (pintype "passive"))
      (node (ref "LED6") (pin "C") (pinfunction "C_C") (pintype "passive"))
      (node (ref "T6") (pin "1") (pinfunction "D_1") (pintype "passive"))
      (node (ref "X2") (pin "6") (pinfunction "1_6") (pintype "passive"))
    )
    (net (code "85") (name "Net-(T6-S)") (class "Default")
      (node (ref "R22") (pin "1") (pinfunction "1_1") (pintype "passive"))
      (node (ref "R6") (pin "2") (pinfunction "2_2") (pintype "passive"))
      (node (ref "T6") (pin "2") (pinfunction "S_2") (pintype "passive"))
    )
    (net (code "86") (name "Net-(T7-D)") (class "Default")
      (node (ref "D7") (pin "A") (pinfunction "A_A") (pintype "passive"))
      (node (ref "LED4") (pin "C") (pinfunction "C_C") (pintype "passive"))
      (node (ref "T7") (pin "1") (pinfunction "D_1") (pintype "passive"))
      (node (ref "X2") (pin "4") (pinfunction "1_4") (pintype "passive"))
    )
    (net (code "87") (name "Net-(T7-S)") (class "Default")
      (node (ref "R23") (pin "1") (pinfunction "1_1") (pintype "passive"))
      (node (ref "R7") (pin "2") (pinfunction "2_2") (pintype "passive"))
      (node (ref "T7") (pin "2") (pinfunction "S_2") (pintype "passive"))
    )
    (net (code "88") (name "Net-(T8-D)") (class "Default")
      (node (ref "D8") (pin "A") (pinfunction "A_A") (pintype "passive"))
      (node (ref "LED2") (pin "C") (pinfunction "C_C") (pintype "passive"))
      (node (ref "T8") (pin "1") (pinfunction "D_1") (pintype "passive"))
      (node (ref "X2") (pin "2") (pinfunction "1_2") (pintype "passive"))
    )
    (net (code "89") (name "Net-(T8-S)") (class "Default")
      (node (ref "R24") (pin "1") (pinfunction "1_1") (pintype "passive"))
      (node (ref "R8") (pin "2") (pinfunction "2_2") (pintype "passive"))
      (node (ref "T8") (pin "2") (pinfunction "S_2") (pintype "passive"))
    )
    (net (code "90") (name "Net-(T9-D)") (class "Default")
      (node (ref "LED18") (pin "C") (pinfunction "C_C") (pintype "passive"))
      (node (ref "T9") (pin "1") (pinfunction "D_1") (pintype "passive"))
      (node (ref "X5") (pin "B2") (pinfunction "B-2_B2") (pintype "passive"))
    )
    (net (code "91") (name "Net-(X2C-1)") (class "Default")
      (node (ref "D7") (pin "C") (pinfunction "C_C") (pintype "passive"))
      (node (ref "F7") (pin "1") (pinfunction "1_1") (pintype "passive"))
      (node (ref "LED3") (pin "C") (pinfunction "C_C") (pintype "passive"))
      (node (ref "X2") (pin "3") (pinfunction "1_3") (pintype "passive"))
    )
    (net (code "92") (name "Net-(X2E-1)") (class "Default")
      (node (ref "D6") (pin "C") (pinfunction "C_C") (pintype "passive"))
      (node (ref "F6") (pin "1") (pinfunction "1_1") (pintype "passive"))
      (node (ref "LED5") (pin "C") (pinfunction "C_C") (pintype "passive"))
      (node (ref "X2") (pin "5") (pinfunction "1_5") (pintype "passive"))
    )
    (net (code "93") (name "Net-(X2G-1)") (class "Default")
      (node (ref "D5") (pin "C") (pinfunction "C_C") (pintype "passive"))
      (node (ref "F5") (pin "1") (pinfunction "1_1") (pintype "passive"))
      (node (ref "LED7") (pin "C") (pinfunction "C_C") (pintype "passive"))
      (node (ref "X2") (pin "7") (pinfunction "1_7") (pintype "passive"))
    )
    (net (code "94") (name "Net-(X3C-1)") (class "Default")
      (node (ref "D3") (pin "C") (pinfunction "C_C") (pintype "passive"))
      (node (ref "F3") (pin "1") (pinfunction "1_1") (pintype "passive"))
      (node (ref "LED11") (pin "C") (pinfunction "C_C") (pintype "passive"))
      (node (ref "X3") (pin "3") (pinfunction "1_3") (pintype "passive"))
    )
    (net (code "95") (name "Net-(X3E-1)") (class "Default")
      (node (ref "D2") (pin "C") (pinfunction "C_C") (pintype "passive"))
      (node (ref "F2") (pin "1") (pinfunction "1_1") (pintype "passive"))
      (node (ref "LED13") (pin "C") (pinfunction "C_C") (pintype "passive"))
      (node (ref "X3") (pin "5") (pinfunction "1_5") (pintype "passive"))
    )
    (net (code "96") (name "Net-(X3G-1)") (class "Default")
      (node (ref "D1") (pin "C") (pinfunction "C_C") (pintype "passive"))
      (node (ref "F1") (pin "1") (pinfunction "1_1") (pintype "passive"))
      (node (ref "LED15") (pin "C") (pinfunction "C_C") (pintype "passive"))
      (node (ref "X3") (pin "7") (pinfunction "1_7") (pintype "passive"))
    )
    (net (code "97") (name "Net-(X4-B-1)") (class "Default")
      (node (ref "R59") (pin "2") (pinfunction "2_2") (pintype "passive"))
      (node (ref "X4") (pin "B1") (pinfunction "B-1_B1") (pintype "passive"))
    )
    (net (code "98") (name "Net-(X4-B-3)") (class "Default")
      (node (ref "R60") (pin "2") (pinfunction "2_2") (pintype "passive"))
      (node (ref "X4") (pin "B3") (pinfunction "B-3_B3") (pintype "passive"))
    )
    (net (code "99") (name "Net-(X4-B-5)") (class "Default")
      (node (ref "R61") (pin "2") (pinfunction "2_2") (pintype "passive"))
      (node (ref "X4") (pin "B5") (pinfunction "B-5_B5") (pintype "passive"))
    )
    (net (code "100") (name "VCC") (class "Default")
      (node (ref "PCB1") (pin "2") (pinfunction "5V0_2") (pintype "power_in"))
      (node (ref "PCB1") (pin "4") (pinfunction "5V0_4") (pintype "power_in"))
    )
    (net (code "101") (name "unconnected-(IC3C-O-Pad8)") (class "Default")
      (node (ref "IC3") (pin "8") (pinfunction "O_8") (pintype "tri_state"))
    )
    (net (code "102") (name "unconnected-(IC3D-O-Pad11)") (class "Default")
      (node (ref "IC3") (pin "11") (pinfunction "O_11") (pintype "tri_state"))
    )
    (net (code "103") (name "unconnected-(PCB1-BL-PadPE_BL)") (class "Default")
      (node (ref "PCB1") (pin "PE_BL") (pinfunction "BL_PE_BL") (pintype "bidirectional"))
    )
    (net (code "104") (name "unconnected-(PCB1-BR-PadPE_BR)") (class "Default")
      (node (ref "PCB1") (pin "PE_BR") (pinfunction "BR_PE_BR") (pintype "bidirectional"))
    )
    (net (code "105") (name "unconnected-(PCB1-GPIO02{slash}SDA1-Pad3)") (class "Default")
      (node (ref "PCB1") (pin "3") (pinfunction "GPIO02/SDA1_3") (pintype "bidirectional"))
    )
    (net (code "106") (name "unconnected-(PCB1-GPIO03{slash}SCL1-Pad5)") (class "Default")
      (node (ref "PCB1") (pin "5") (pinfunction "GPIO03/SCL1_5") (pintype "bidirectional"))
    )
    (net (code "107") (name "unconnected-(PCB1-GPIO27{slash}GEN2-Pad13)") (class "Default")
      (node (ref "PCB1") (pin "13") (pinfunction "GPIO27/GEN2_13") (pintype "bidirectional"))
    )
    (net (code "108") (name "unconnected-(PCB1-ID_SC-Pad28)") (class "Default")
      (node (ref "PCB1") (pin "28") (pinfunction "ID_SC_28") (pintype "bidirectional"))
    )
    (net (code "109") (name "unconnected-(PCB1-ID_SD-Pad27)") (class "Default")
      (node (ref "PCB1") (pin "27") (pinfunction "ID_SD_27") (pintype "bidirectional"))
    )
    (net (code "110") (name "unconnected-(PCB1-TL-PadPE_TL)") (class "Default")
      (node (ref "PCB1") (pin "PE_TL") (pinfunction "TL_PE_TL") (pintype "bidirectional"))
    )
    (net (code "111") (name "unconnected-(PCB1-TR-PadPE_TR)") (class "Default")
      (node (ref "PCB1") (pin "PE_TR") (pinfunction "TR_PE_TR") (pintype "bidirectional"))
    )
    (net (code "112") (name "unconnected-(X4--1-PadA1)") (class "Default")
      (node (ref "X4") (pin "A1") (pinfunction "-1_A1") (pintype "passive"))
    )
    (net (code "113") (name "unconnected-(X4--2-PadA2)") (class "Default")
      (node (ref "X4") (pin "A2") (pinfunction "-2_A2") (pintype "passive"))
    )
    (net (code "114") (name "unconnected-(X4--3-PadA3)") (class "Default")
      (node (ref "X4") (pin "A3") (pinfunction "-3_A3") (pintype "passive"))
    )
    (net (code "115") (name "unconnected-(X4--4-PadA4)") (class "Default")
      (node (ref "X4") (pin "A4") (pinfunction "-4_A4") (pintype "passive"))
    )
    (net (code "116") (name "unconnected-(X4--5-PadA5)") (class "Default")
      (node (ref "X4") (pin "A5") (pinfunction "-5_A5") (pintype "passive"))
    )
    (net (code "117") (name "unconnected-(X4--6-PadA6)") (class "Default")
      (node (ref "X4") (pin "A6") (pinfunction "-6_A6") (pintype "passive"))
    )
    (net (code "118") (name "unconnected-(X5--1-PadA1)") (class "Default")
      (node (ref "X5") (pin "A1") (pinfunction "-1_A1") (pintype "passive"))
    )
    (net (code "119") (name "unconnected-(X5--2-PadA2)") (class "Default")
      (node (ref "X5") (pin "A2") (pinfunction "-2_A2") (pintype "passive"))
    )
    (net (code "120") (name "unconnected-(X6--1-PadA1)") (class "Default")
      (node (ref "X6") (pin "A1") (pinfunction "-1_A1") (pintype "passive"))
    )
    (net (code "121") (name "unconnected-(X6--2-PadA2)") (class "Default")
      (node (ref "X6") (pin "A2") (pinfunction "-2_A2") (pintype "passive"))
    )
    (net (code "122") (name "unconnected-(X6--3-PadA3)") (class "Default")
      (node (ref "X6") (pin "A3") (pinfunction "-3_A3") (pintype "passive"))
    )
  )
)
